# NixieClock.net
KiCad netlist of a schematic drawn in EAGLE
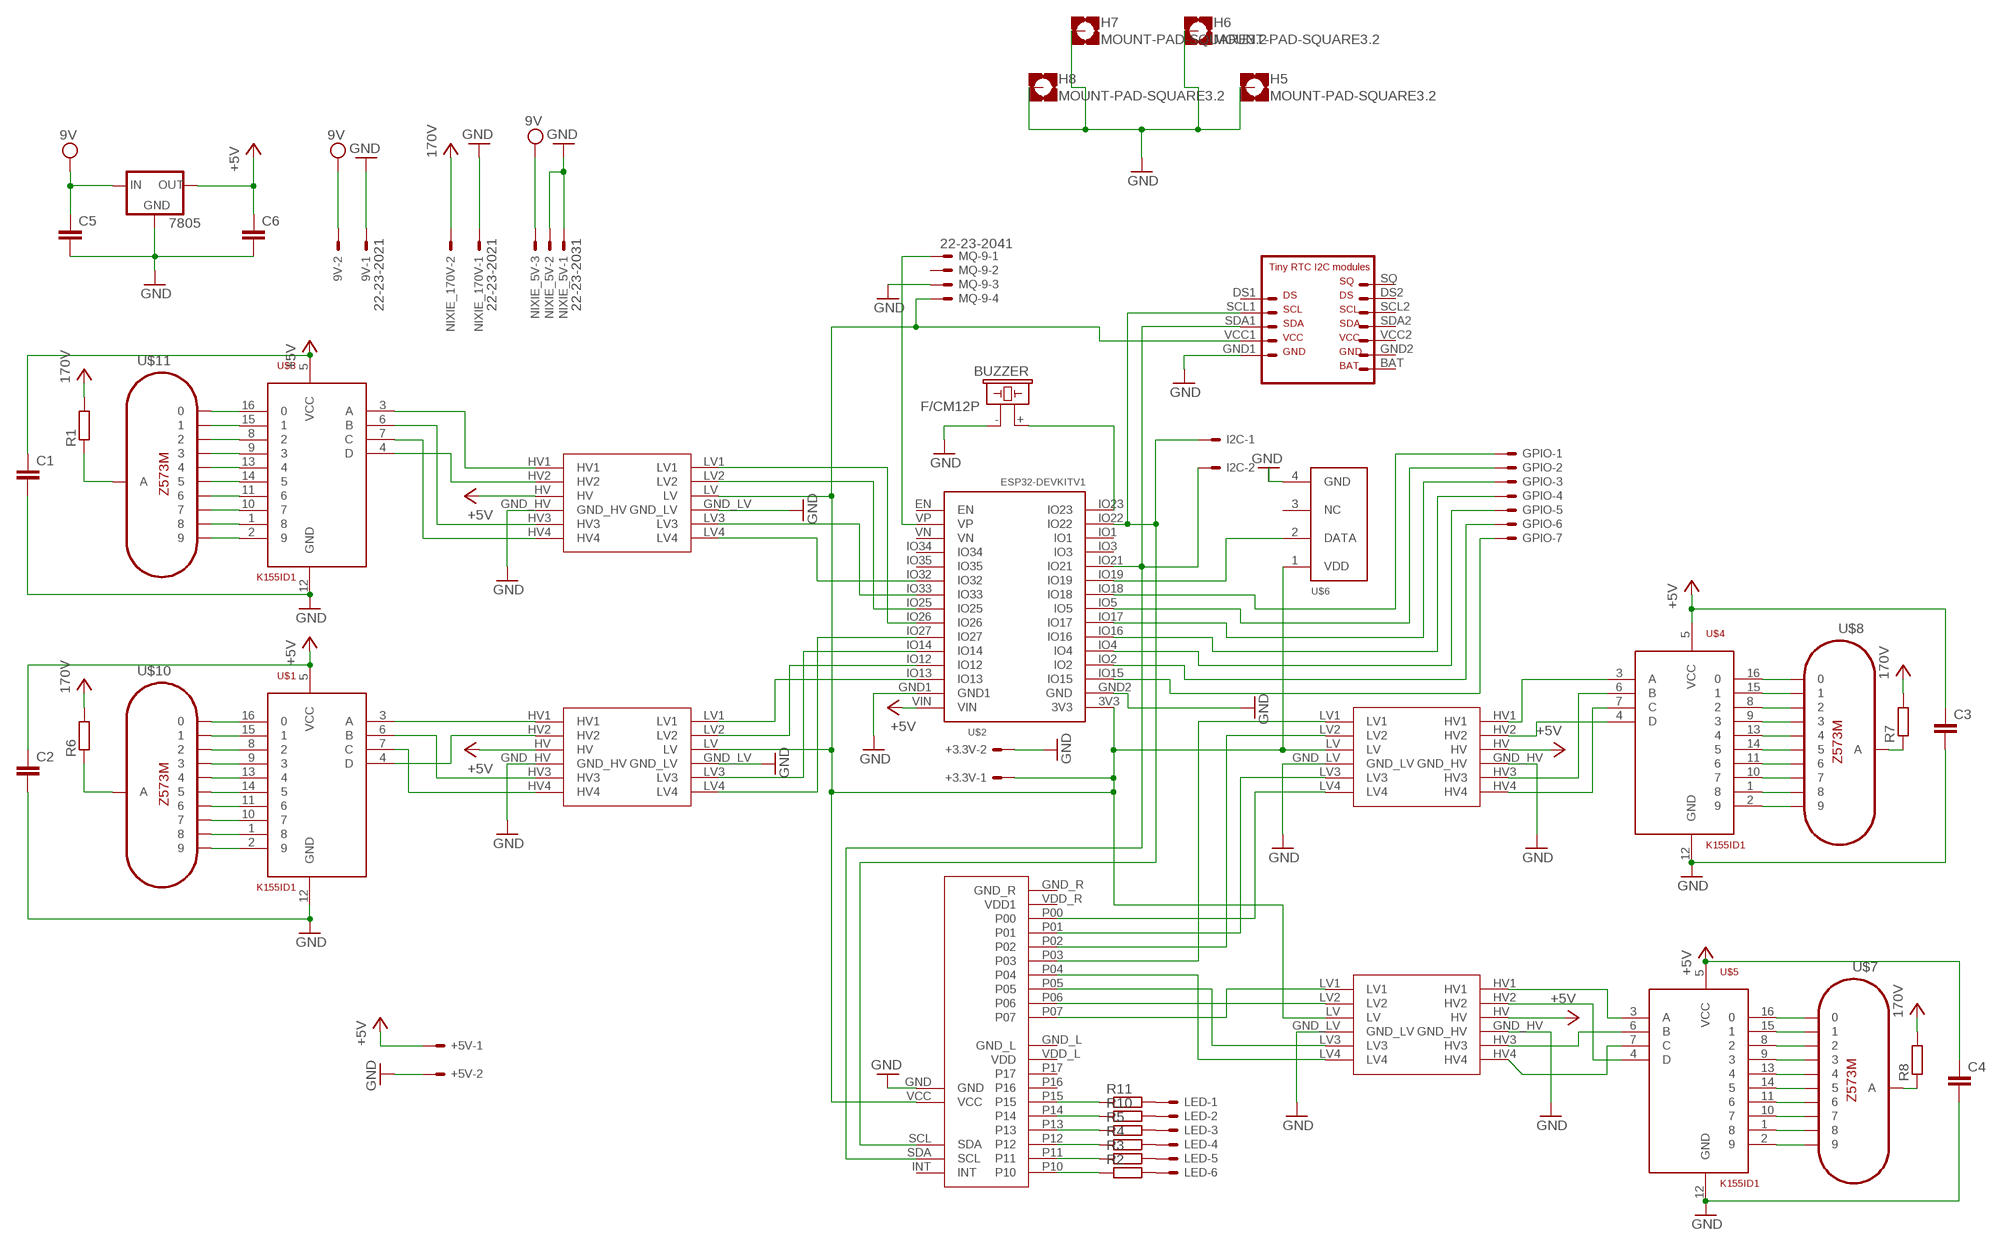
[diagram p0: schematic, sheet 1]

(export (version "E")
  (design (tool "Eeschema 10.0.6"))
  (components
    (comp (ref "+3.3V")
      (value "KK-156-2")
      (footprint "eagle-import:KK-156-2")
      (fields (field (name "MF") "MOLEX"))
      (libsource (lib "eagle-import") (part "KK-156-2"))
    )
    (comp (ref "+5V")
      (value "KK-156-2")
      (footprint "eagle-import:KK-156-2")
      (fields (field (name "MF") "MOLEX"))
      (libsource (lib "eagle-import") (part "KK-156-2"))
    )
    (comp (ref "9V")
      (value "22-23-2021")
      (footprint "eagle-import:22-23-2021")
      (fields (field (name "MF") "MOLEX"))
      (libsource (lib "eagle-import") (part "22-23-2021"))
    )
    (comp (ref "7805")
      (value "78XXS")
      (footprint "eagle-import:78XXS")
      (libsource (lib "eagle-import") (part "78XXS"))
    )
    (comp (ref "BUZZER")
      (value "F/CM12P")
      (footprint "eagle-import:F_CM12P")
      (libsource (lib "eagle-import") (part "F/CM12P"))
    )
    (comp (ref "C1")
      (value "C2,5-3")
      (footprint "eagle-import:C2.5-3")
      (libsource (lib "eagle-import") (part "C2,5-3"))
    )
    (comp (ref "C2")
      (value "C2,5-3")
      (footprint "eagle-import:C2.5-3")
      (libsource (lib "eagle-import") (part "C2,5-3"))
    )
    (comp (ref "C3")
      (value "C2,5-3")
      (footprint "eagle-import:C2.5-3")
      (libsource (lib "eagle-import") (part "C2,5-3"))
    )
    (comp (ref "C4")
      (value "C2,5-3")
      (footprint "eagle-import:C2.5-3")
      (libsource (lib "eagle-import") (part "C2,5-3"))
    )
    (comp (ref "C5")
      (value "C2,5-3")
      (footprint "eagle-import:C2.5-3")
      (libsource (lib "eagle-import") (part "C2,5-3"))
    )
    (comp (ref "C6")
      (value "C2,5-3")
      (footprint "eagle-import:C2.5-3")
      (libsource (lib "eagle-import") (part "C2,5-3"))
    )
    (comp (ref "GPIO")
      (value "KK-156-7")
      (footprint "eagle-import:KK-156-7")
      (fields (field (name "MF") "MOLEX"))
      (libsource (lib "eagle-import") (part "KK-156-7"))
    )
    (comp (ref "H5")
      (value "MOUNT-PAD-SQUARE3.2")
      (footprint "eagle-import:3,2-PAD-SQUARE")
      (libsource (lib "eagle-import") (part "MOUNT-PAD-SQUARE3.2"))
    )
    (comp (ref "H6")
      (value "MOUNT-PAD-SQUARE3.2")
      (footprint "eagle-import:3,2-PAD-SQUARE")
      (libsource (lib "eagle-import") (part "MOUNT-PAD-SQUARE3.2"))
    )
    (comp (ref "H7")
      (value "MOUNT-PAD-SQUARE3.2")
      (footprint "eagle-import:3,2-PAD-SQUARE")
      (libsource (lib "eagle-import") (part "MOUNT-PAD-SQUARE3.2"))
    )
    (comp (ref "H8")
      (value "MOUNT-PAD-SQUARE3.2")
      (footprint "eagle-import:3,2-PAD-SQUARE")
      (libsource (lib "eagle-import") (part "MOUNT-PAD-SQUARE3.2"))
    )
    (comp (ref "I2C")
      (value "KK-156-2")
      (footprint "eagle-import:KK-156-2")
      (fields (field (name "MF") "MOLEX"))
      (libsource (lib "eagle-import") (part "KK-156-2"))
    )
    (comp (ref "LED")
      (value "KK-156-6")
      (footprint "eagle-import:KK-156-6")
      (fields (field (name "MF") "MOLEX"))
      (libsource (lib "eagle-import") (part "KK-156-6"))
    )
    (comp (ref "MQ-9")
      (value "22-23-2041")
      (footprint "eagle-import:22-23-2041")
      (fields (field (name "MF") "MOLEX") (field (name "MPN") "wyświetlacz I2C"))
      (libsource (lib "eagle-import") (part "22-23-2041"))
    )
    (comp (ref "NIXIE_5V")
      (value "22-23-2031")
      (footprint "eagle-import:22-23-2031")
      (fields (field (name "MF") "MOLEX"))
      (libsource (lib "eagle-import") (part "22-23-2031"))
    )
    (comp (ref "NIXIE_170V")
      (value "22-23-2021")
      (footprint "eagle-import:22-23-2021")
      (fields (field (name "MF") "MOLEX"))
      (libsource (lib "eagle-import") (part "22-23-2021"))
    )
    (comp (ref "R1")
      (value "R-EU_0204/7")
      (footprint "eagle-import:0204_7")
      (libsource (lib "eagle-import") (part "R-EU_0204/7"))
    )
    (comp (ref "R2")
      (value "R-EU_0204/7")
      (footprint "eagle-import:0204_7")
      (libsource (lib "eagle-import") (part "R-EU_0204/7"))
    )
    (comp (ref "R3")
      (value "R-EU_0204/7")
      (footprint "eagle-import:0204_7")
      (libsource (lib "eagle-import") (part "R-EU_0204/7"))
    )
    (comp (ref "R4")
      (value "R-EU_0204/7")
      (footprint "eagle-import:0204_7")
      (libsource (lib "eagle-import") (part "R-EU_0204/7"))
    )
    (comp (ref "R5")
      (value "R-EU_0204/7")
      (footprint "eagle-import:0204_7")
      (libsource (lib "eagle-import") (part "R-EU_0204/7"))
    )
    (comp (ref "R6")
      (value "R-EU_0204/7")
      (footprint "eagle-import:0204_7")
      (libsource (lib "eagle-import") (part "R-EU_0204/7"))
    )
    (comp (ref "R7")
      (value "R-EU_0204/7")
      (footprint "eagle-import:0204_7")
      (libsource (lib "eagle-import") (part "R-EU_0204/7"))
    )
    (comp (ref "R8")
      (value "R-EU_0204/7")
      (footprint "eagle-import:0204_7")
      (libsource (lib "eagle-import") (part "R-EU_0204/7"))
    )
    (comp (ref "R10")
      (value "R-EU_0204/7")
      (footprint "eagle-import:0204_7")
      (libsource (lib "eagle-import") (part "R-EU_0204/7"))
    )
    (comp (ref "R11")
      (value "R-EU_0204/7")
      (footprint "eagle-import:0204_7")
      (libsource (lib "eagle-import") (part "R-EU_0204/7"))
    )
    (comp (ref "STEP_UP_$")
      (value "LEVEL-CONVERTER")
      (footprint "eagle-import:LEVEL-CONVERTER")
      (libsource (lib "eagle-import") (part "LEVEL-CONVERTER"))
    )
    (comp (ref "U$1")
      (value "K155ID1")
      (footprint "eagle-import:DIP16-2.54-19.2X7.62MM")
      (libsource (lib "eagle-import") (part "K155ID1"))
    )
    (comp (ref "U$2")
      (value "ESP32DEVKITV1")
      (footprint "eagle-import:ESP32-DEVKITV1")
      (libsource (lib "eagle-import") (part "ESP32DEVKITV1"))
    )
    (comp (ref "U$3")
      (value "K155ID1")
      (footprint "eagle-import:DIP16-2.54-19.2X7.62MM")
      (libsource (lib "eagle-import") (part "K155ID1"))
    )
    (comp (ref "U$4")
      (value "K155ID1")
      (footprint "eagle-import:DIP16-2.54-19.2X7.62MM")
      (libsource (lib "eagle-import") (part "K155ID1"))
    )
    (comp (ref "U$5")
      (value "K155ID1")
      (footprint "eagle-import:DIP16-2.54-19.2X7.62MM")
      (libsource (lib "eagle-import") (part "K155ID1"))
    )
    (comp (ref "U$6")
      (value "DHT11")
      (footprint "eagle-import:DHT11")
      (libsource (lib "eagle-import") (part "DHT11"))
    )
    (comp (ref "U$7")
      (value "Z573M")
      (footprint "eagle-import:Z573M")
      (libsource (lib "eagle-import") (part "Z573M"))
    )
    (comp (ref "U$8")
      (value "Z573M")
      (footprint "eagle-import:Z573M")
      (libsource (lib "eagle-import") (part "Z573M"))
    )
    (comp (ref "U$9")
      (value "RTC")
      (footprint "eagle-import:RTC")
      (libsource (lib "eagle-import") (part "RTC"))
    )
    (comp (ref "U$10")
      (value "Z573M")
      (footprint "eagle-import:Z573M")
      (libsource (lib "eagle-import") (part "Z573M"))
    )
    (comp (ref "U$11")
      (value "Z573M")
      (footprint "eagle-import:Z573M")
      (libsource (lib "eagle-import") (part "Z573M"))
    )
    (comp (ref "U$12")
      (value "LEVEL-CONVERTER")
      (footprint "eagle-import:LEVEL-CONVERTER")
      (libsource (lib "eagle-import") (part "LEVEL-CONVERTER"))
    )
    (comp (ref "U$13")
      (value "LEVEL-CONVERTER")
      (footprint "eagle-import:LEVEL-CONVERTER")
      (libsource (lib "eagle-import") (part "LEVEL-CONVERTER"))
    )
    (comp (ref "U$15")
      (value "LEVEL-CONVERTER")
      (footprint "eagle-import:LEVEL-CONVERTER")
      (libsource (lib "eagle-import") (part "LEVEL-CONVERTER"))
    )
    (comp (ref "U$16")
      (value "PCF8575")
      (footprint "eagle-import:PCF8575")
      (libsource (lib "eagle-import") (part "PCF8575"))
    )
  )
  (nets
    (net (code "1") (name "+5V") (class "Default")
      (node (ref "+5V") (pin "1") (pinfunction "S_1") (pintype "passive"))
      (node (ref "7805") (pin "OUT") (pinfunction "OUT_OUT") (pintype "passive"))
      (node (ref "C1") (pin "1") (pinfunction "1_1") (pintype "passive"))
      (node (ref "C2") (pin "1") (pinfunction "1_1") (pintype "passive"))
      (node (ref "C3") (pin "1") (pinfunction "1_1") (pintype "passive"))
      (node (ref "C4") (pin "1") (pinfunction "1_1") (pintype "passive"))
      (node (ref "C6") (pin "1") (pinfunction "1_1") (pintype "passive"))
      (node (ref "STEP_UP_$") (pin "HV") (pinfunction "HV_HV") (pintype "bidirectional"))
      (node (ref "U$1") (pin "5") (pinfunction "VCC_5") (pintype "bidirectional"))
      (node (ref "U$12") (pin "HV") (pinfunction "HV_HV") (pintype "bidirectional"))
      (node (ref "U$13") (pin "HV") (pinfunction "HV_HV") (pintype "bidirectional"))
      (node (ref "U$15") (pin "HV") (pinfunction "HV_HV") (pintype "bidirectional"))
      (node (ref "U$2") (pin "VIN") (pinfunction "VIN_VIN") (pintype "bidirectional"))
      (node (ref "U$3") (pin "5") (pinfunction "VCC_5") (pintype "bidirectional"))
      (node (ref "U$4") (pin "5") (pinfunction "VCC_5") (pintype "bidirectional"))
      (node (ref "U$5") (pin "5") (pinfunction "VCC_5") (pintype "bidirectional"))
    )
    (net (code "2") (name "170V") (class "Default")
      (node (ref "7805") (pin "IN") (pinfunction "IN_IN") (pintype "input"))
      (node (ref "9V") (pin "2") (pinfunction "S_2") (pintype "passive"))
      (node (ref "C5") (pin "1") (pinfunction "1_1") (pintype "passive"))
      (node (ref "NIXIE_170V") (pin "2") (pinfunction "S_2") (pintype "passive"))
      (node (ref "NIXIE_5V") (pin "3") (pinfunction "S_3") (pintype "passive"))
      (node (ref "R1") (pin "2") (pinfunction "2_2") (pintype "passive"))
      (node (ref "R6") (pin "2") (pinfunction "2_2") (pintype "passive"))
      (node (ref "R7") (pin "2") (pinfunction "2_2") (pintype "passive"))
      (node (ref "R8") (pin "2") (pinfunction "2_2") (pintype "passive"))
    )
    (net (code "3") (name "GND") (class "Default")
      (node (ref "+3.3V") (pin "2") (pinfunction "S_2") (pintype "passive"))
      (node (ref "+5V") (pin "2") (pinfunction "S_2") (pintype "passive"))
      (node (ref "7805") (pin "GND") (pinfunction "GND_GND") (pintype "input"))
      (node (ref "9V") (pin "1") (pinfunction "S_1") (pintype "passive"))
      (node (ref "BUZZER") (pin "-") (pinfunction "2_-") (pintype "passive"))
      (node (ref "C1") (pin "2") (pinfunction "2_2") (pintype "passive"))
      (node (ref "C2") (pin "2") (pinfunction "2_2") (pintype "passive"))
      (node (ref "C3") (pin "2") (pinfunction "2_2") (pintype "passive"))
      (node (ref "C4") (pin "2") (pinfunction "2_2") (pintype "passive"))
      (node (ref "C5") (pin "2") (pinfunction "2_2") (pintype "passive"))
      (node (ref "C6") (pin "2") (pinfunction "2_2") (pintype "passive"))
      (node (ref "H5") (pin "B3,2") (pinfunction "MOUNT_B3,2") (pintype "passive"))
      (node (ref "H6") (pin "B3,2") (pinfunction "MOUNT_B3,2") (pintype "passive"))
      (node (ref "H7") (pin "B3,2") (pinfunction "MOUNT_B3,2") (pintype "passive"))
      (node (ref "H8") (pin "B3,2") (pinfunction "MOUNT_B3,2") (pintype "passive"))
      (node (ref "MQ-9") (pin "3") (pinfunction "S_3") (pintype "passive"))
      (node (ref "NIXIE_170V") (pin "1") (pinfunction "S_1") (pintype "passive"))
      (node (ref "NIXIE_5V") (pin "1") (pinfunction "S_1") (pintype "passive"))
      (node (ref "NIXIE_5V") (pin "2") (pinfunction "S_2") (pintype "passive"))
      (node (ref "STEP_UP_$") (pin "GND_HV") (pinfunction "GND_HV_GND_HV") (pintype "bidirectional"))
      (node (ref "STEP_UP_$") (pin "GND_LV") (pinfunction "GND_LV_GND_LV") (pintype "bidirectional"))
      (node (ref "U$1") (pin "12") (pinfunction "GND_12") (pintype "bidirectional"))
      (node (ref "U$12") (pin "GND_HV") (pinfunction "GND_HV_GND_HV") (pintype "bidirectional"))
      (node (ref "U$12") (pin "GND_LV") (pinfunction "GND_LV_GND_LV") (pintype "bidirectional"))
      (node (ref "U$13") (pin "GND_HV") (pinfunction "GND_HV_GND_HV") (pintype "bidirectional"))
      (node (ref "U$13") (pin "GND_LV") (pinfunction "GND_LV_GND_LV") (pintype "bidirectional"))
      (node (ref "U$15") (pin "GND_HV") (pinfunction "GND_HV_GND_HV") (pintype "bidirectional"))
      (node (ref "U$15") (pin "GND_LV") (pinfunction "GND_LV_GND_LV") (pintype "bidirectional"))
      (node (ref "U$16") (pin "GND") (pinfunction "GND_GND") (pintype "bidirectional"))
      (node (ref "U$2") (pin "GND1") (pinfunction "GND1_GND1") (pintype "bidirectional"))
      (node (ref "U$2") (pin "GND2") (pinfunction "GND_GND2") (pintype "bidirectional"))
      (node (ref "U$3") (pin "12") (pinfunction "GND_12") (pintype "bidirectional"))
      (node (ref "U$4") (pin "12") (pinfunction "GND_12") (pintype "bidirectional"))
      (node (ref "U$5") (pin "12") (pinfunction "GND_12") (pintype "bidirectional"))
      (node (ref "U$6") (pin "4") (pinfunction "GND_4") (pintype "power_in"))
      (node (ref "U$9") (pin "GND1") (pinfunction "GND1_GND1") (pintype "passive"))
    )
    (net (code "4") (name "Net-(+3.3VA-S)") (class "Default")
      (node (ref "+3.3V") (pin "1") (pinfunction "S_1") (pintype "passive"))
      (node (ref "MQ-9") (pin "4") (pinfunction "S_4") (pintype "passive"))
      (node (ref "STEP_UP_$") (pin "LV") (pinfunction "LV_LV") (pintype "bidirectional"))
      (node (ref "U$12") (pin "LV") (pinfunction "LV_LV") (pintype "bidirectional"))
      (node (ref "U$13") (pin "LV") (pinfunction "LV_LV") (pintype "bidirectional"))
      (node (ref "U$15") (pin "LV") (pinfunction "LV_LV") (pintype "bidirectional"))
      (node (ref "U$16") (pin "VCC") (pinfunction "VCC_VCC") (pintype "bidirectional"))
      (node (ref "U$2") (pin "3V3") (pinfunction "3V3_3V3") (pintype "bidirectional"))
      (node (ref "U$6") (pin "1") (pinfunction "VDD_1") (pintype "power_in"))
      (node (ref "U$9") (pin "VCC1") (pinfunction "VCC1_VCC1") (pintype "passive"))
    )
    (net (code "5") (name "Net-(BUZZER-1)") (class "Default")
      (node (ref "BUZZER") (pin "+") (pinfunction "1_+") (pintype "passive"))
      (node (ref "U$2") (pin "IO23") (pinfunction "IO23_IO23") (pintype "bidirectional"))
    )
    (net (code "6") (name "Net-(GPIOA-S)") (class "Default")
      (node (ref "GPIO") (pin "1") (pinfunction "S_1") (pintype "passive"))
      (node (ref "U$2") (pin "IO18") (pinfunction "IO18_IO18") (pintype "bidirectional"))
    )
    (net (code "7") (name "Net-(GPIOB-S)") (class "Default")
      (node (ref "GPIO") (pin "2") (pinfunction "S_2") (pintype "passive"))
      (node (ref "U$2") (pin "IO5") (pinfunction "IO5_IO5") (pintype "bidirectional"))
    )
    (net (code "8") (name "Net-(GPIOC-S)") (class "Default")
      (node (ref "GPIO") (pin "3") (pinfunction "S_3") (pintype "passive"))
      (node (ref "U$2") (pin "IO17") (pinfunction "IO17_IO17") (pintype "bidirectional"))
    )
    (net (code "9") (name "Net-(GPIOD-S)") (class "Default")
      (node (ref "GPIO") (pin "4") (pinfunction "S_4") (pintype "passive"))
      (node (ref "U$2") (pin "IO16") (pinfunction "IO16_IO16") (pintype "bidirectional"))
    )
    (net (code "10") (name "Net-(GPIOE-S)") (class "Default")
      (node (ref "GPIO") (pin "5") (pinfunction "S_5") (pintype "passive"))
      (node (ref "U$2") (pin "IO4") (pinfunction "IO4_IO4") (pintype "bidirectional"))
    )
    (net (code "11") (name "Net-(GPIOF-S)") (class "Default")
      (node (ref "GPIO") (pin "6") (pinfunction "S_6") (pintype "passive"))
      (node (ref "U$2") (pin "IO2") (pinfunction "IO2_IO2") (pintype "bidirectional"))
    )
    (net (code "12") (name "Net-(GPIOG-S)") (class "Default")
      (node (ref "GPIO") (pin "7") (pinfunction "S_7") (pintype "passive"))
      (node (ref "U$2") (pin "IO15") (pinfunction "IO15_IO15") (pintype "bidirectional"))
    )
    (net (code "13") (name "Net-(I2CA-S)") (class "Default")
      (node (ref "I2C") (pin "1") (pinfunction "S_1") (pintype "passive"))
      (node (ref "U$16") (pin "SCL") (pinfunction "SDA_SCL") (pintype "bidirectional"))
      (node (ref "U$2") (pin "IO22") (pinfunction "IO22_IO22") (pintype "bidirectional"))
      (node (ref "U$9") (pin "SCL1") (pinfunction "SCL1_SCL1") (pintype "passive"))
    )
    (net (code "14") (name "Net-(I2CB-S)") (class "Default")
      (node (ref "I2C") (pin "2") (pinfunction "S_2") (pintype "passive"))
      (node (ref "U$16") (pin "SDA") (pinfunction "SCL_SDA") (pintype "bidirectional"))
      (node (ref "U$2") (pin "IO21") (pinfunction "IO21_IO21") (pintype "bidirectional"))
      (node (ref "U$9") (pin "SDA1") (pinfunction "SDA1_SDA1") (pintype "passive"))
    )
    (net (code "15") (name "Net-(LEDA-S)") (class "Default")
      (node (ref "LED") (pin "1") (pinfunction "S_1") (pintype "passive"))
      (node (ref "R11") (pin "2") (pinfunction "2_2") (pintype "passive"))
    )
    (net (code "16") (name "Net-(LEDB-S)") (class "Default")
      (node (ref "LED") (pin "2") (pinfunction "S_2") (pintype "passive"))
      (node (ref "R10") (pin "2") (pinfunction "2_2") (pintype "passive"))
    )
    (net (code "17") (name "Net-(LEDC-S)") (class "Default")
      (node (ref "LED") (pin "3") (pinfunction "S_3") (pintype "passive"))
      (node (ref "R5") (pin "2") (pinfunction "2_2") (pintype "passive"))
    )
    (net (code "18") (name "Net-(LEDD-S)") (class "Default")
      (node (ref "LED") (pin "4") (pinfunction "S_4") (pintype "passive"))
      (node (ref "R4") (pin "2") (pinfunction "2_2") (pintype "passive"))
    )
    (net (code "19") (name "Net-(LEDE-S)") (class "Default")
      (node (ref "LED") (pin "5") (pinfunction "S_5") (pintype "passive"))
      (node (ref "R3") (pin "2") (pinfunction "2_2") (pintype "passive"))
    )
    (net (code "20") (name "Net-(LEDF-S)") (class "Default")
      (node (ref "LED") (pin "6") (pinfunction "S_6") (pintype "passive"))
      (node (ref "R2") (pin "2") (pinfunction "2_2") (pintype "passive"))
    )
    (net (code "21") (name "Net-(MQ-9A-S)") (class "Default")
      (node (ref "MQ-9") (pin "1") (pinfunction "S_1") (pintype "passive"))
      (node (ref "U$2") (pin "VP") (pinfunction "VP_VP") (pintype "bidirectional"))
    )
    (net (code "22") (name "Net-(R1-Pad1)") (class "Default")
      (node (ref "R1") (pin "1") (pinfunction "1_1") (pintype "passive"))
      (node (ref "U$11") (pin "A") (pinfunction "A_A") (pintype "bidirectional"))
    )
    (net (code "23") (name "Net-(R2-Pad1)") (class "Default")
      (node (ref "R2") (pin "1") (pinfunction "1_1") (pintype "passive"))
      (node (ref "U$16") (pin "P10") (pinfunction "P10_P10") (pintype "bidirectional"))
    )
    (net (code "24") (name "Net-(R3-Pad1)") (class "Default")
      (node (ref "R3") (pin "1") (pinfunction "1_1") (pintype "passive"))
      (node (ref "U$16") (pin "P11") (pinfunction "P11_P11") (pintype "bidirectional"))
    )
    (net (code "25") (name "Net-(R4-Pad1)") (class "Default")
      (node (ref "R4") (pin "1") (pinfunction "1_1") (pintype "passive"))
      (node (ref "U$16") (pin "P12") (pinfunction "P12_P12") (pintype "bidirectional"))
    )
    (net (code "26") (name "Net-(R5-Pad1)") (class "Default")
      (node (ref "R5") (pin "1") (pinfunction "1_1") (pintype "passive"))
      (node (ref "U$16") (pin "P13") (pinfunction "P13_P13") (pintype "bidirectional"))
    )
    (net (code "27") (name "Net-(R6-Pad1)") (class "Default")
      (node (ref "R6") (pin "1") (pinfunction "1_1") (pintype "passive"))
      (node (ref "U$10") (pin "A") (pinfunction "A_A") (pintype "bidirectional"))
    )
    (net (code "28") (name "Net-(R7-Pad1)") (class "Default")
      (node (ref "R7") (pin "1") (pinfunction "1_1") (pintype "passive"))
      (node (ref "U$8") (pin "A") (pinfunction "A_A") (pintype "bidirectional"))
    )
    (net (code "29") (name "Net-(R8-Pad1)") (class "Default")
      (node (ref "R8") (pin "1") (pinfunction "1_1") (pintype "passive"))
      (node (ref "U$7") (pin "A") (pinfunction "A_A") (pintype "bidirectional"))
    )
    (net (code "30") (name "Net-(R10-Pad1)") (class "Default")
      (node (ref "R10") (pin "1") (pinfunction "1_1") (pintype "passive"))
      (node (ref "U$16") (pin "P14") (pinfunction "P14_P14") (pintype "bidirectional"))
    )
    (net (code "31") (name "Net-(R11-Pad1)") (class "Default")
      (node (ref "R11") (pin "1") (pinfunction "1_1") (pintype "passive"))
      (node (ref "U$16") (pin "P15") (pinfunction "P15_P15") (pintype "bidirectional"))
    )
    (net (code "32") (name "Net-(STEP_UP_$-PadLV1)") (class "Default")
      (node (ref "STEP_UP_$") (pin "LV1") (pinfunction "LV1_LV1") (pintype "bidirectional"))
      (node (ref "U$16") (pin "P07") (pinfunction "P07_P07") (pintype "bidirectional"))
    )
    (net (code "33") (name "Net-(STEP_UP_$-PadLV2)") (class "Default")
      (node (ref "STEP_UP_$") (pin "LV2") (pinfunction "LV2_LV2") (pintype "bidirectional"))
      (node (ref "U$16") (pin "P06") (pinfunction "P06_P06") (pintype "bidirectional"))
    )
    (net (code "34") (name "Net-(STEP_UP_$-PadLV3)") (class "Default")
      (node (ref "STEP_UP_$") (pin "LV3") (pinfunction "LV3_LV3") (pintype "bidirectional"))
      (node (ref "U$16") (pin "P05") (pinfunction "P05_P05") (pintype "bidirectional"))
    )
    (net (code "35") (name "Net-(STEP_UP_$-PadLV4)") (class "Default")
      (node (ref "STEP_UP_$") (pin "LV4") (pinfunction "LV4_LV4") (pintype "bidirectional"))
      (node (ref "U$16") (pin "P04") (pinfunction "P04_P04") (pintype "bidirectional"))
    )
    (net (code "36") (name "Net-(U$1-0)") (class "Default")
      (node (ref "U$1") (pin "16") (pinfunction "0_16") (pintype "bidirectional"))
      (node (ref "U$10") (pin "K0") (pinfunction "0_K0") (pintype "bidirectional"))
    )
    (net (code "37") (name "Net-(U$1-1)") (class "Default")
      (node (ref "U$1") (pin "15") (pinfunction "1_15") (pintype "bidirectional"))
      (node (ref "U$10") (pin "K1") (pinfunction "1_K1") (pintype "bidirectional"))
    )
    (net (code "38") (name "Net-(U$1-2)") (class "Default")
      (node (ref "U$1") (pin "8") (pinfunction "2_8") (pintype "bidirectional"))
      (node (ref "U$10") (pin "K2") (pinfunction "2_K2") (pintype "bidirectional"))
    )
    (net (code "39") (name "Net-(U$1-3)") (class "Default")
      (node (ref "U$1") (pin "9") (pinfunction "3_9") (pintype "bidirectional"))
      (node (ref "U$10") (pin "K3") (pinfunction "3_K3") (pintype "bidirectional"))
    )
    (net (code "40") (name "Net-(U$1-4)") (class "Default")
      (node (ref "U$1") (pin "13") (pinfunction "4_13") (pintype "bidirectional"))
      (node (ref "U$10") (pin "K4") (pinfunction "4_K4") (pintype "bidirectional"))
    )
    (net (code "41") (name "Net-(U$1-5)") (class "Default")
      (node (ref "U$1") (pin "14") (pinfunction "5_14") (pintype "bidirectional"))
      (node (ref "U$10") (pin "K5") (pinfunction "5_K5") (pintype "bidirectional"))
    )
    (net (code "42") (name "Net-(U$1-6)") (class "Default")
      (node (ref "U$1") (pin "11") (pinfunction "6_11") (pintype "bidirectional"))
      (node (ref "U$10") (pin "K6") (pinfunction "6_K6") (pintype "bidirectional"))
    )
    (net (code "43") (name "Net-(U$1-7)") (class "Default")
      (node (ref "U$1") (pin "10") (pinfunction "7_10") (pintype "bidirectional"))
      (node (ref "U$10") (pin "K7") (pinfunction "7_K7") (pintype "bidirectional"))
    )
    (net (code "44") (name "Net-(U$1-8)") (class "Default")
      (node (ref "U$1") (pin "1") (pinfunction "8_1") (pintype "bidirectional"))
      (node (ref "U$10") (pin "K8") (pinfunction "8_K8") (pintype "bidirectional"))
    )
    (net (code "45") (name "Net-(U$1-9)") (class "Default")
      (node (ref "U$1") (pin "2") (pinfunction "9_2") (pintype "bidirectional"))
      (node (ref "U$10") (pin "K9") (pinfunction "9_K9") (pintype "bidirectional"))
    )
    (net (code "46") (name "Net-(U$1-A)") (class "Default")
      (node (ref "U$1") (pin "3") (pinfunction "A_3") (pintype "bidirectional"))
      (node (ref "U$12") (pin "HV1") (pinfunction "HV1_HV1") (pintype "bidirectional"))
    )
    (net (code "47") (name "Net-(U$1-B)") (class "Default")
      (node (ref "U$1") (pin "6") (pinfunction "B_6") (pintype "bidirectional"))
      (node (ref "U$12") (pin "HV3") (pinfunction "HV3_HV3") (pintype "bidirectional"))
    )
    (net (code "48") (name "Net-(U$1-C)") (class "Default")
      (node (ref "U$1") (pin "7") (pinfunction "C_7") (pintype "bidirectional"))
      (node (ref "U$12") (pin "HV4") (pinfunction "HV4_HV4") (pintype "bidirectional"))
    )
    (net (code "49") (name "Net-(U$1-D)") (class "Default")
      (node (ref "U$1") (pin "4") (pinfunction "D_4") (pintype "bidirectional"))
      (node (ref "U$12") (pin "HV2") (pinfunction "HV2_HV2") (pintype "bidirectional"))
    )
    (net (code "50") (name "Net-(U$3-A)") (class "Default")
      (node (ref "U$13") (pin "HV1") (pinfunction "HV1_HV1") (pintype "bidirectional"))
      (node (ref "U$3") (pin "3") (pinfunction "A_3") (pintype "bidirectional"))
    )
    (net (code "51") (name "Net-(U$3-B)") (class "Default")
      (node (ref "U$13") (pin "HV3") (pinfunction "HV3_HV3") (pintype "bidirectional"))
      (node (ref "U$3") (pin "6") (pinfunction "B_6") (pintype "bidirectional"))
    )
    (net (code "52") (name "Net-(U$3-C)") (class "Default")
      (node (ref "U$13") (pin "HV4") (pinfunction "HV4_HV4") (pintype "bidirectional"))
      (node (ref "U$3") (pin "7") (pinfunction "C_7") (pintype "bidirectional"))
    )
    (net (code "53") (name "Net-(U$3-D)") (class "Default")
      (node (ref "U$13") (pin "HV2") (pinfunction "HV2_HV2") (pintype "bidirectional"))
      (node (ref "U$3") (pin "4") (pinfunction "D_4") (pintype "bidirectional"))
    )
    (net (code "54") (name "Net-(U$4-0)") (class "Default")
      (node (ref "U$4") (pin "16") (pinfunction "0_16") (pintype "bidirectional"))
      (node (ref "U$8") (pin "K0") (pinfunction "0_K0") (pintype "bidirectional"))
    )
    (net (code "55") (name "Net-(U$4-1)") (class "Default")
      (node (ref "U$4") (pin "15") (pinfunction "1_15") (pintype "bidirectional"))
      (node (ref "U$8") (pin "K1") (pinfunction "1_K1") (pintype "bidirectional"))
    )
    (net (code "56") (name "Net-(U$4-2)") (class "Default")
      (node (ref "U$4") (pin "8") (pinfunction "2_8") (pintype "bidirectional"))
      (node (ref "U$8") (pin "K2") (pinfunction "2_K2") (pintype "bidirectional"))
    )
    (net (code "57") (name "Net-(U$4-3)") (class "Default")
      (node (ref "U$4") (pin "9") (pinfunction "3_9") (pintype "bidirectional"))
      (node (ref "U$8") (pin "K3") (pinfunction "3_K3") (pintype "bidirectional"))
    )
    (net (code "58") (name "Net-(U$4-4)") (class "Default")
      (node (ref "U$4") (pin "13") (pinfunction "4_13") (pintype "bidirectional"))
      (node (ref "U$8") (pin "K4") (pinfunction "4_K4") (pintype "bidirectional"))
    )
    (net (code "59") (name "Net-(U$4-5)") (class "Default")
      (node (ref "U$4") (pin "14") (pinfunction "5_14") (pintype "bidirectional"))
      (node (ref "U$8") (pin "K5") (pinfunction "5_K5") (pintype "bidirectional"))
    )
    (net (code "60") (name "Net-(U$4-6)") (class "Default")
      (node (ref "U$4") (pin "11") (pinfunction "6_11") (pintype "bidirectional"))
      (node (ref "U$8") (pin "K6") (pinfunction "6_K6") (pintype "bidirectional"))
    )
    (net (code "61") (name "Net-(U$4-7)") (class "Default")
      (node (ref "U$4") (pin "10") (pinfunction "7_10") (pintype "bidirectional"))
      (node (ref "U$8") (pin "K7") (pinfunction "7_K7") (pintype "bidirectional"))
    )
    (net (code "62") (name "Net-(U$4-8)") (class "Default")
      (node (ref "U$4") (pin "1") (pinfunction "8_1") (pintype "bidirectional"))
      (node (ref "U$8") (pin "K8") (pinfunction "8_K8") (pintype "bidirectional"))
    )
    (net (code "63") (name "Net-(U$4-9)") (class "Default")
      (node (ref "U$4") (pin "2") (pinfunction "9_2") (pintype "bidirectional"))
      (node (ref "U$8") (pin "K9") (pinfunction "9_K9") (pintype "bidirectional"))
    )
    (net (code "64") (name "Net-(U$4-A)") (class "Default")
      (node (ref "U$15") (pin "HV1") (pinfunction "HV1_HV1") (pintype "bidirectional"))
      (node (ref "U$4") (pin "3") (pinfunction "A_3") (pintype "bidirectional"))
    )
    (net (code "65") (name "Net-(U$4-B)") (class "Default")
      (node (ref "U$15") (pin "HV3") (pinfunction "HV3_HV3") (pintype "bidirectional"))
      (node (ref "U$4") (pin "6") (pinfunction "B_6") (pintype "bidirectional"))
    )
    (net (code "66") (name "Net-(U$4-C)") (class "Default")
      (node (ref "U$15") (pin "HV4") (pinfunction "HV4_HV4") (pintype "bidirectional"))
      (node (ref "U$4") (pin "7") (pinfunction "C_7") (pintype "bidirectional"))
    )
    (net (code "67") (name "Net-(U$4-D)") (class "Default")
      (node (ref "U$15") (pin "HV2") (pinfunction "HV2_HV2") (pintype "bidirectional"))
      (node (ref "U$4") (pin "4") (pinfunction "D_4") (pintype "bidirectional"))
    )
    (net (code "68") (name "Net-(U$5-0)") (class "Default")
      (node (ref "U$5") (pin "16") (pinfunction "0_16") (pintype "bidirectional"))
      (node (ref "U$7") (pin "K0") (pinfunction "0_K0") (pintype "bidirectional"))
    )
    (net (code "69") (name "Net-(U$5-1)") (class "Default")
      (node (ref "U$5") (pin "15") (pinfunction "1_15") (pintype "bidirectional"))
      (node (ref "U$7") (pin "K1") (pinfunction "1_K1") (pintype "bidirectional"))
    )
    (net (code "70") (name "Net-(U$5-2)") (class "Default")
      (node (ref "U$5") (pin "8") (pinfunction "2_8") (pintype "bidirectional"))
      (node (ref "U$7") (pin "K2") (pinfunction "2_K2") (pintype "bidirectional"))
    )
    (net (code "71") (name "Net-(U$5-3)") (class "Default")
      (node (ref "U$5") (pin "9") (pinfunction "3_9") (pintype "bidirectional"))
      (node (ref "U$7") (pin "K3") (pinfunction "3_K3") (pintype "bidirectional"))
    )
    (net (code "72") (name "Net-(U$5-4)") (class "Default")
      (node (ref "U$5") (pin "13") (pinfunction "4_13") (pintype "bidirectional"))
      (node (ref "U$7") (pin "K4") (pinfunction "4_K4") (pintype "bidirectional"))
    )
    (net (code "73") (name "Net-(U$5-5)") (class "Default")
      (node (ref "U$5") (pin "14") (pinfunction "5_14") (pintype "bidirectional"))
      (node (ref "U$7") (pin "K5") (pinfunction "5_K5") (pintype "bidirectional"))
    )
    (net (code "74") (name "Net-(U$5-6)") (class "Default")
      (node (ref "U$5") (pin "11") (pinfunction "6_11") (pintype "bidirectional"))
      (node (ref "U$7") (pin "K6") (pinfunction "6_K6") (pintype "bidirectional"))
    )
    (net (code "75") (name "Net-(U$5-7)") (class "Default")
      (node (ref "U$5") (pin "10") (pinfunction "7_10") (pintype "bidirectional"))
      (node (ref "U$7") (pin "K7") (pinfunction "7_K7") (pintype "bidirectional"))
    )
    (net (code "76") (name "Net-(U$5-8)") (class "Default")
      (node (ref "U$5") (pin "1") (pinfunction "8_1") (pintype "bidirectional"))
      (node (ref "U$7") (pin "K8") (pinfunction "8_K8") (pintype "bidirectional"))
    )
    (net (code "77") (name "Net-(U$5-9)") (class "Default")
      (node (ref "U$5") (pin "2") (pinfunction "9_2") (pintype "bidirectional"))
      (node (ref "U$7") (pin "K9") (pinfunction "9_K9") (pintype "bidirectional"))
    )
    (net (code "78") (name "Net-(U$5-A)") (class "Default")
      (node (ref "STEP_UP_$") (pin "HV1") (pinfunction "HV1_HV1") (pintype "bidirectional"))
      (node (ref "U$5") (pin "3") (pinfunction "A_3") (pintype "bidirectional"))
    )
    (net (code "79") (name "Net-(U$5-B)") (class "Default")
      (node (ref "STEP_UP_$") (pin "HV3") (pinfunction "HV3_HV3") (pintype "bidirectional"))
      (node (ref "U$5") (pin "6") (pinfunction "B_6") (pintype "bidirectional"))
    )
    (net (code "80") (name "Net-(U$5-C)") (class "Default")
      (node (ref "STEP_UP_$") (pin "HV4") (pinfunction "HV4_HV4") (pintype "bidirectional"))
      (node (ref "U$5") (pin "7") (pinfunction "C_7") (pintype "bidirectional"))
    )
    (net (code "81") (name "Net-(U$5-D)") (class "Default")
      (node (ref "STEP_UP_$") (pin "HV2") (pinfunction "HV2_HV2") (pintype "bidirectional"))
      (node (ref "U$5") (pin "4") (pinfunction "D_4") (pintype "bidirectional"))
    )
    (net (code "82") (name "Net-(U$6-DATA)") (class "Default")
      (node (ref "U$2") (pin "IO19") (pinfunction "IO19_IO19") (pintype "bidirectional"))
      (node (ref "U$6") (pin "2") (pinfunction "DATA_2") (pintype "bidirectional"))
    )
    (net (code "83") (name "Net-(U$11-0)") (class "Default")
      (node (ref "U$11") (pin "K0") (pinfunction "0_K0") (pintype "bidirectional"))
      (node (ref "U$3") (pin "16") (pinfunction "0_16") (pintype "bidirectional"))
    )
    (net (code "84") (name "Net-(U$11-1)") (class "Default")
      (node (ref "U$11") (pin "K1") (pinfunction "1_K1") (pintype "bidirectional"))
      (node (ref "U$3") (pin "15") (pinfunction "1_15") (pintype "bidirectional"))
    )
    (net (code "85") (name "Net-(U$11-2)") (class "Default")
      (node (ref "U$11") (pin "K2") (pinfunction "2_K2") (pintype "bidirectional"))
      (node (ref "U$3") (pin "8") (pinfunction "2_8") (pintype "bidirectional"))
    )
    (net (code "86") (name "Net-(U$11-3)") (class "Default")
      (node (ref "U$11") (pin "K3") (pinfunction "3_K3") (pintype "bidirectional"))
      (node (ref "U$3") (pin "9") (pinfunction "3_9") (pintype "bidirectional"))
    )
    (net (code "87") (name "Net-(U$11-4)") (class "Default")
      (node (ref "U$11") (pin "K4") (pinfunction "4_K4") (pintype "bidirectional"))
      (node (ref "U$3") (pin "13") (pinfunction "4_13") (pintype "bidirectional"))
    )
    (net (code "88") (name "Net-(U$11-5)") (class "Default")
      (node (ref "U$11") (pin "K5") (pinfunction "5_K5") (pintype "bidirectional"))
      (node (ref "U$3") (pin "14") (pinfunction "5_14") (pintype "bidirectional"))
    )
    (net (code "89") (name "Net-(U$11-6)") (class "Default")
      (node (ref "U$11") (pin "K6") (pinfunction "6_K6") (pintype "bidirectional"))
      (node (ref "U$3") (pin "11") (pinfunction "6_11") (pintype "bidirectional"))
    )
    (net (code "90") (name "Net-(U$11-7)") (class "Default")
      (node (ref "U$11") (pin "K7") (pinfunction "7_K7") (pintype "bidirectional"))
      (node (ref "U$3") (pin "10") (pinfunction "7_10") (pintype "bidirectional"))
    )
    (net (code "91") (name "Net-(U$11-8)") (class "Default")
      (node (ref "U$11") (pin "K8") (pinfunction "8_K8") (pintype "bidirectional"))
      (node (ref "U$3") (pin "1") (pinfunction "8_1") (pintype "bidirectional"))
    )
    (net (code "92") (name "Net-(U$11-9)") (class "Default")
      (node (ref "U$11") (pin "K9") (pinfunction "9_K9") (pintype "bidirectional"))
      (node (ref "U$3") (pin "2") (pinfunction "9_2") (pintype "bidirectional"))
    )
    (net (code "93") (name "Net-(U$12-PadLV1)") (class "Default")
      (node (ref "U$12") (pin "LV1") (pinfunction "LV1_LV1") (pintype "bidirectional"))
      (node (ref "U$2") (pin "IO13") (pinfunction "IO13_IO13") (pintype "bidirectional"))
    )
    (net (code "94") (name "Net-(U$12-PadLV2)") (class "Default")
      (node (ref "U$12") (pin "LV2") (pinfunction "LV2_LV2") (pintype "bidirectional"))
      (node (ref "U$2") (pin "IO12") (pinfunction "IO12_IO12") (pintype "bidirectional"))
    )
    (net (code "95") (name "Net-(U$12-PadLV3)") (class "Default")
      (node (ref "U$12") (pin "LV3") (pinfunction "LV3_LV3") (pintype "bidirectional"))
      (node (ref "U$2") (pin "IO14") (pinfunction "IO14_IO14") (pintype "bidirectional"))
    )
    (net (code "96") (name "Net-(U$12-PadLV4)") (class "Default")
      (node (ref "U$12") (pin "LV4") (pinfunction "LV4_LV4") (pintype "bidirectional"))
      (node (ref "U$2") (pin "IO27") (pinfunction "IO27_IO27") (pintype "bidirectional"))
    )
    (net (code "97") (name "Net-(U$13-PadLV1)") (class "Default")
      (node (ref "U$13") (pin "LV1") (pinfunction "LV1_LV1") (pintype "bidirectional"))
      (node (ref "U$2") (pin "IO26") (pinfunction "IO26_IO26") (pintype "bidirectional"))
    )
    (net (code "98") (name "Net-(U$13-PadLV2)") (class "Default")
      (node (ref "U$13") (pin "LV2") (pinfunction "LV2_LV2") (pintype "bidirectional"))
      (node (ref "U$2") (pin "IO25") (pinfunction "IO25_IO25") (pintype "bidirectional"))
    )
    (net (code "99") (name "Net-(U$13-PadLV3)") (class "Default")
      (node (ref "U$13") (pin "LV3") (pinfunction "LV3_LV3") (pintype "bidirectional"))
      (node (ref "U$2") (pin "IO33") (pinfunction "IO33_IO33") (pintype "bidirectional"))
    )
    (net (code "100") (name "Net-(U$13-PadLV4)") (class "Default")
      (node (ref "U$13") (pin "LV4") (pinfunction "LV4_LV4") (pintype "bidirectional"))
      (node (ref "U$2") (pin "IO32") (pinfunction "IO32_IO32") (pintype "bidirectional"))
    )
    (net (code "101") (name "Net-(U$15-PadLV1)") (class "Default")
      (node (ref "U$15") (pin "LV1") (pinfunction "LV1_LV1") (pintype "bidirectional"))
      (node (ref "U$16") (pin "P03") (pinfunction "P03_P03") (pintype "bidirectional"))
    )
    (net (code "102") (name "Net-(U$15-PadLV2)") (class "Default")
      (node (ref "U$15") (pin "LV2") (pinfunction "LV2_LV2") (pintype "bidirectional"))
      (node (ref "U$16") (pin "P02") (pinfunction "P02_P02") (pintype "bidirectional"))
    )
    (net (code "103") (name "Net-(U$15-PadLV3)") (class "Default")
      (node (ref "U$15") (pin "LV3") (pinfunction "LV3_LV3") (pintype "bidirectional"))
      (node (ref "U$16") (pin "P01") (pinfunction "P01_P01") (pintype "bidirectional"))
    )
    (net (code "104") (name "Net-(U$15-PadLV4)") (class "Default")
      (node (ref "U$15") (pin "LV4") (pinfunction "LV4_LV4") (pintype "bidirectional"))
      (node (ref "U$16") (pin "P00") (pinfunction "P00_P00") (pintype "bidirectional"))
    )
    (net (code "105") (name "unconnected-(MQ-9B-S-Pad2)") (class "Default")
      (node (ref "MQ-9") (pin "2") (pinfunction "S_2") (pintype "passive"))
    )
    (net (code "106") (name "unconnected-(U$2-PadEN)") (class "Default")
      (node (ref "U$2") (pin "EN") (pinfunction "EN_EN") (pintype "bidirectional"))
    )
    (net (code "107") (name "unconnected-(U$2-PadIO1)") (class "Default")
      (node (ref "U$2") (pin "IO1") (pinfunction "IO1_IO1") (pintype "bidirectional"))
    )
    (net (code "108") (name "unconnected-(U$2-PadIO3)") (class "Default")
      (node (ref "U$2") (pin "IO3") (pinfunction "IO3_IO3") (pintype "bidirectional"))
    )
    (net (code "109") (name "unconnected-(U$2-PadIO34)") (class "Default")
      (node (ref "U$2") (pin "IO34") (pinfunction "IO34_IO34") (pintype "bidirectional"))
    )
    (net (code "110") (name "unconnected-(U$2-PadIO35)") (class "Default")
      (node (ref "U$2") (pin "IO35") (pinfunction "IO35_IO35") (pintype "bidirectional"))
    )
    (net (code "111") (name "unconnected-(U$2-PadVN)") (class "Default")
      (node (ref "U$2") (pin "VN") (pinfunction "VN_VN") (pintype "bidirectional"))
    )
    (net (code "112") (name "unconnected-(U$6-NC-Pad3)") (class "Default")
      (node (ref "U$6") (pin "3") (pinfunction "NC_3") (pintype "bidirectional"))
    )
    (net (code "113") (name "unconnected-(U$9-PadBAT)") (class "Default")
      (node (ref "U$9") (pin "BAT") (pinfunction "BAT_BAT") (pintype "passive"))
    )
    (net (code "114") (name "unconnected-(U$9-PadDS1)") (class "Default")
      (node (ref "U$9") (pin "DS1") (pinfunction "DS1_DS1") (pintype "passive"))
    )
    (net (code "115") (name "unconnected-(U$9-PadDS2)") (class "Default")
      (node (ref "U$9") (pin "DS2") (pinfunction "DS2_DS2") (pintype "passive"))
    )
    (net (code "116") (name "unconnected-(U$9-PadGND2)") (class "Default")
      (node (ref "U$9") (pin "GND2") (pinfunction "GND2_GND2") (pintype "passive"))
    )
    (net (code "117") (name "unconnected-(U$9-PadSCL2)") (class "Default")
      (node (ref "U$9") (pin "SCL2") (pinfunction "SCL2_SCL2") (pintype "passive"))
    )
    (net (code "118") (name "unconnected-(U$9-PadSDA2)") (class "Default")
      (node (ref "U$9") (pin "SDA2") (pinfunction "SDA2_SDA2") (pintype "passive"))
    )
    (net (code "119") (name "unconnected-(U$9-PadSQ)") (class "Default")
      (node (ref "U$9") (pin "SQ") (pinfunction "SQ_SQ") (pintype "passive"))
    )
    (net (code "120") (name "unconnected-(U$9-PadVCC2)") (class "Default")
      (node (ref "U$9") (pin "VCC2") (pinfunction "VCC2_VCC2") (pintype "passive"))
    )
    (net (code "121") (name "unconnected-(U$16-PadGND_L)") (class "Default")
      (node (ref "U$16") (pin "GND_L") (pinfunction "GND_L_GND_L") (pintype "bidirectional"))
    )
    (net (code "122") (name "unconnected-(U$16-PadGND_R)") (class "Default")
      (node (ref "U$16") (pin "GND_R") (pinfunction "GND_R_GND_R") (pintype "bidirectional"))
    )
    (net (code "123") (name "unconnected-(U$16-PadINT)") (class "Default")
      (node (ref "U$16") (pin "INT") (pinfunction "INT_INT") (pintype "bidirectional"))
    )
    (net (code "124") (name "unconnected-(U$16-PadP16)") (class "Default")
      (node (ref "U$16") (pin "P16") (pinfunction "P16_P16") (pintype "bidirectional"))
    )
    (net (code "125") (name "unconnected-(U$16-PadP17)") (class "Default")
      (node (ref "U$16") (pin "P17") (pinfunction "P17_P17") (pintype "bidirectional"))
    )
    (net (code "126") (name "unconnected-(U$16-VDD-PadVDD_L)") (class "Default")
      (node (ref "U$16") (pin "VDD_L") (pinfunction "VDD_VDD_L") (pintype "bidirectional"))
    )
    (net (code "127") (name "unconnected-(U$16-VDD1-PadVDD_R)") (class "Default")
      (node (ref "U$16") (pin "VDD_R") (pinfunction "VDD1_VDD_R") (pintype "bidirectional"))
    )
  )
)
